# MethaneFlux.net
KiCad netlist of a schematic drawn in EAGLE
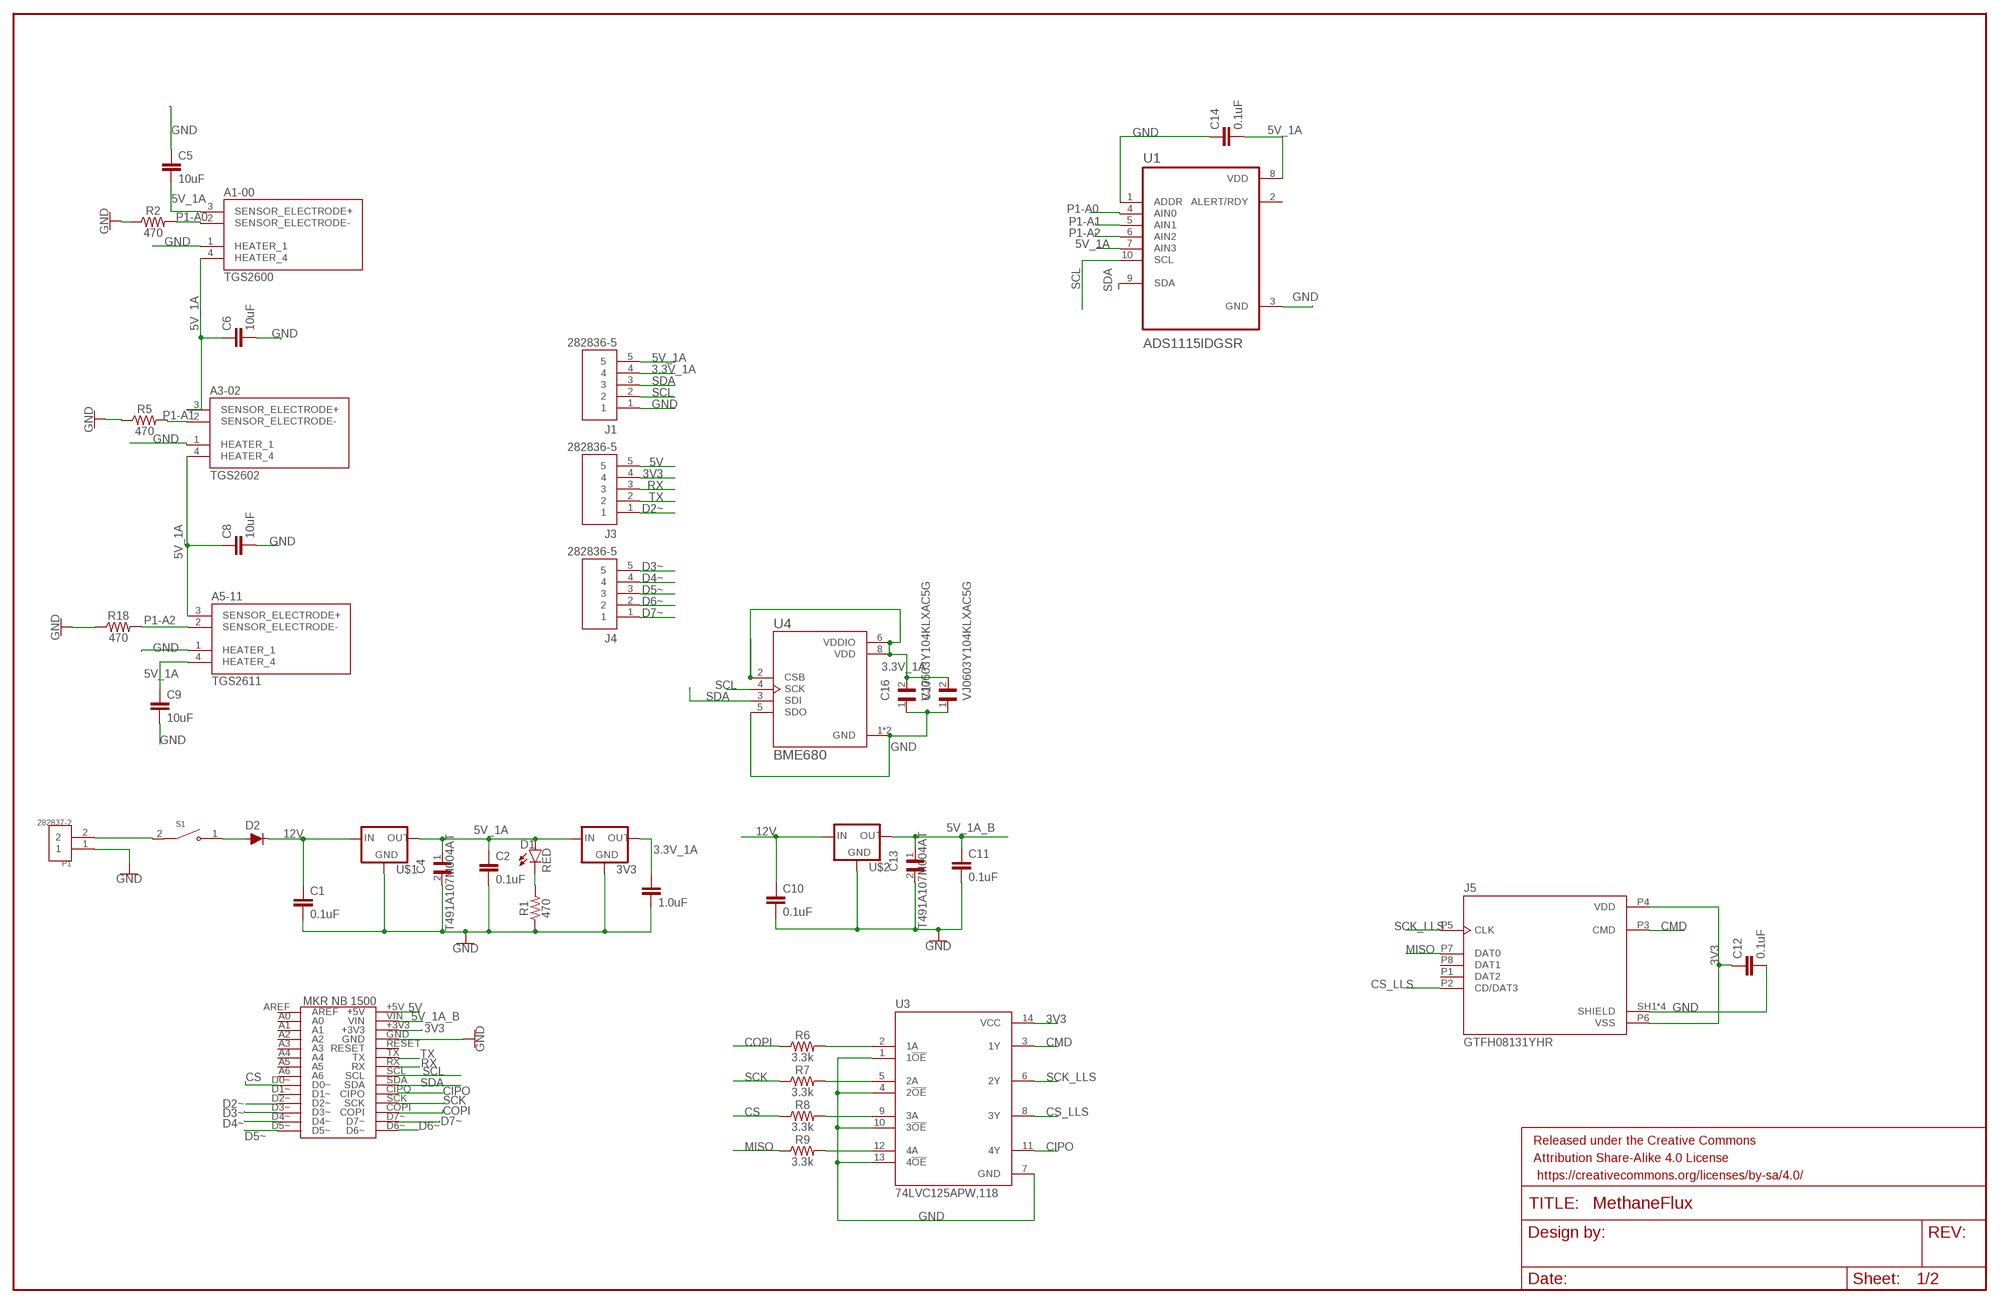
[diagram p0: schematic, sheet 1]
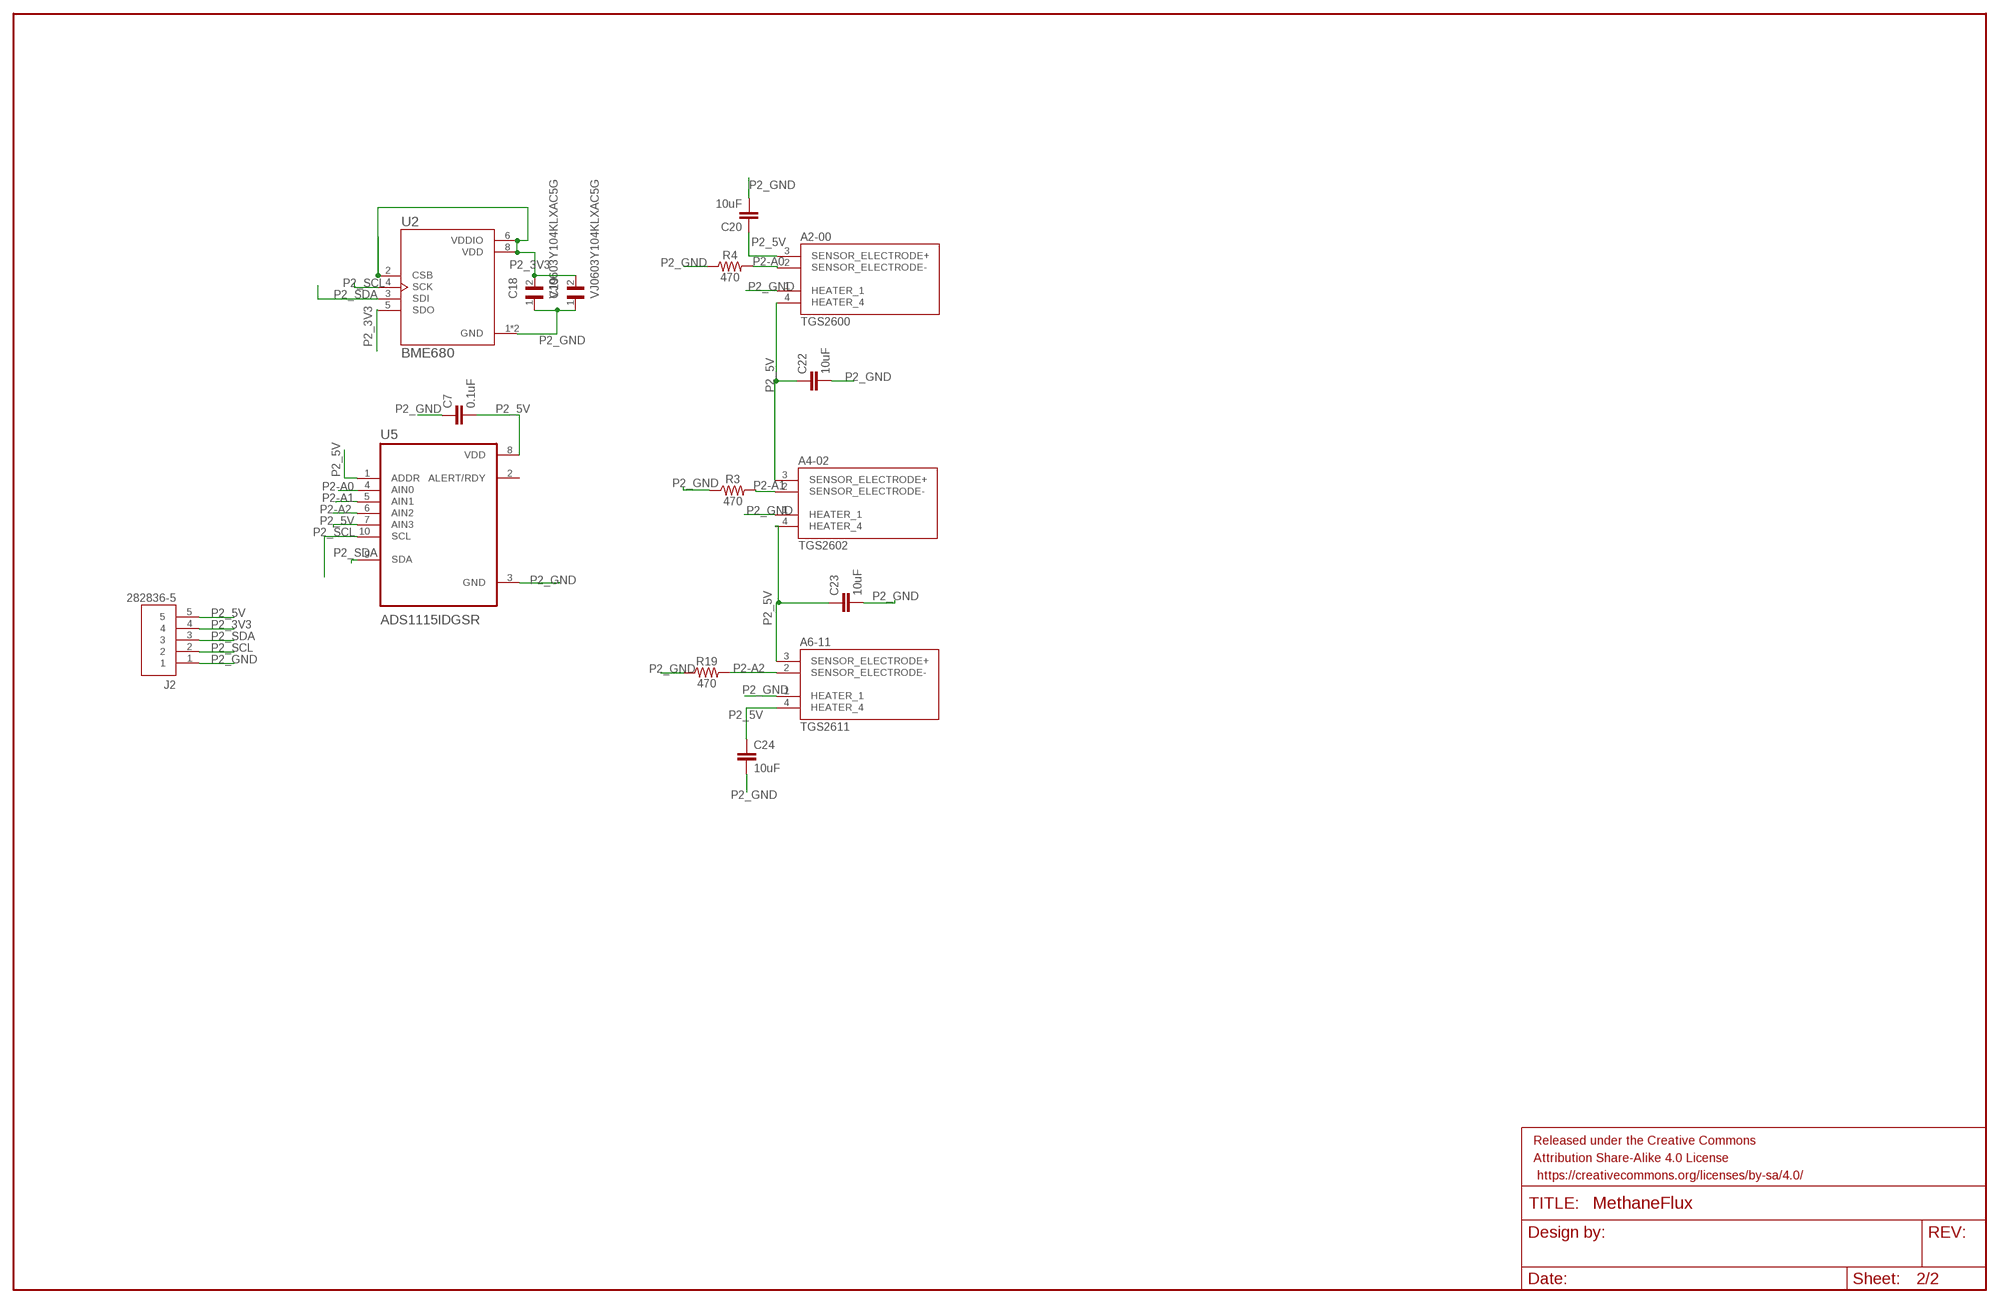
[diagram p1: schematic, sheet 2]

(export (version "E")
  (design (tool "Eeschema 10.0.6"))
  (components
    (comp (ref "A2-00")
      (value "TGS2600")
      (footprint "eagle-import:TO255P920H830-4")
      (fields (field (name "MF") "Figaro"))
      (libsource (lib "eagle-import") (part "TGS2600"))
    )
    (comp (ref "A4-02")
      (value "TGS2602")
      (footprint "eagle-import:TGS2602")
      (libsource (lib "eagle-import") (part "TGS2602"))
    )
    (comp (ref "A6-11")
      (value "TGS2611")
      (footprint "eagle-import:TGS2611")
      (libsource (lib "eagle-import") (part "TGS2611"))
    )
    (comp (ref "C7")
      (value "0.1uF")
      (footprint "eagle-import:0603")
      (libsource (lib "eagle-import") (part "0.1UF-0603-25V-5%"))
    )
    (comp (ref "C18")
      (value "VJ0603Y104KLXAC5G")
      (footprint "eagle-import:CAPC1608X92N")
      (fields (field (name "MF") "Vishay"))
      (libsource (lib "eagle-import") (part "VJ0603Y104KLXAC5G"))
    )
    (comp (ref "C19")
      (value "VJ0603Y104KLXAC5G")
      (footprint "eagle-import:CAPC1608X92N")
      (fields (field (name "MF") "Vishay"))
      (libsource (lib "eagle-import") (part "VJ0603Y104KLXAC5G"))
    )
    (comp (ref "C20")
      (value "10uF")
      (footprint "eagle-import:0603")
      (libsource (lib "eagle-import") (part "10UF-0603-6.3V-20%"))
    )
    (comp (ref "C22")
      (value "10uF")
      (footprint "eagle-import:0603")
      (libsource (lib "eagle-import") (part "10UF-0603-6.3V-20%"))
    )
    (comp (ref "C23")
      (value "10uF")
      (footprint "eagle-import:0603")
      (libsource (lib "eagle-import") (part "10UF-0603-6.3V-20%"))
    )
    (comp (ref "C24")
      (value "10uF")
      (footprint "eagle-import:0603")
      (libsource (lib "eagle-import") (part "10UF-0603-6.3V-20%"))
    )
    (comp (ref "FRAME2")
      (value "FRAME-LEDGER")
      (footprint "eagle-import:CREATIVE_COMMONS")
      (libsource (lib "eagle-import") (part "FRAME-LEDGER"))
    )
    (comp (ref "J2")
      (value "282836-5")
      (footprint "eagle-import:TE_282836-5")
      (fields (field (name "MF") "TE Connectivity"))
      (libsource (lib "eagle-import") (part "282836-5"))
    )
    (comp (ref "R3")
      (value "470")
      (footprint "eagle-import:0603")
      (libsource (lib "eagle-import") (part "470OHM-0603-1/10W-1%"))
    )
    (comp (ref "R4")
      (value "470")
      (footprint "eagle-import:0603")
      (libsource (lib "eagle-import") (part "470OHM-0603-1/10W-1%"))
    )
    (comp (ref "R19")
      (value "470")
      (footprint "eagle-import:0603")
      (libsource (lib "eagle-import") (part "470OHM-0603-1/10W-1%"))
    )
    (comp (ref "U2")
      (value "BME680")
      (footprint "eagle-import:PSON80P300X300X100-8N")
      (fields (field (name "MF") "Bosch Sensortec"))
      (libsource (lib "eagle-import") (part "BME680"))
    )
    (comp (ref "U5")
      (value "ADS1115IDGSR")
      (footprint "eagle-import:SOP50P490X110-10N")
      (fields (field (name "MF") "Texas Instruments"))
      (libsource (lib "eagle-import") (part "ADS1115IDGSR"))
    )
    (comp (ref "3V3")
      (value "V_REG_LD1117VXXLD1117-SMD")
      (footprint "eagle-import:SOT223")
      (libsource (lib "eagle-import") (part "V_REG_LD1117VXXLD1117-SMD"))
    )
    (comp (ref "A1-00")
      (value "TGS2600")
      (footprint "eagle-import:TO255P920H830-4")
      (fields (field (name "MF") "Figaro"))
      (libsource (lib "eagle-import") (part "TGS2600"))
    )
    (comp (ref "A3-02")
      (value "TGS2602")
      (footprint "eagle-import:TGS2602")
      (libsource (lib "eagle-import") (part "TGS2602"))
    )
    (comp (ref "A5-11")
      (value "TGS2611")
      (footprint "eagle-import:TGS2611")
      (libsource (lib "eagle-import") (part "TGS2611"))
    )
    (comp (ref "C1")
      (value "0.1uF")
      (footprint "eagle-import:0603")
      (libsource (lib "eagle-import") (part "0.1UF-0603-25V-5%"))
    )
    (comp (ref "C2")
      (value "0.1uF")
      (footprint "eagle-import:0603")
      (libsource (lib "eagle-import") (part "0.1UF-0603-25V-5%"))
    )
    (comp (ref "C3")
      (value "1.0uF")
      (footprint "eagle-import:0603")
      (libsource (lib "eagle-import") (part "1.0UF-0603-16V-10%"))
    )
    (comp (ref "C4")
      (value "T491A107M004AT")
      (footprint "eagle-import:CAPC3216X110N")
      (fields (field (name "MF") "KEMET"))
      (libsource (lib "eagle-import") (part "T491A107M004AT"))
    )
    (comp (ref "C5")
      (value "10uF")
      (footprint "eagle-import:0603")
      (libsource (lib "eagle-import") (part "10UF-0603-6.3V-20%"))
    )
    (comp (ref "C6")
      (value "10uF")
      (footprint "eagle-import:0603")
      (libsource (lib "eagle-import") (part "10UF-0603-6.3V-20%"))
    )
    (comp (ref "C8")
      (value "10uF")
      (footprint "eagle-import:0603")
      (libsource (lib "eagle-import") (part "10UF-0603-6.3V-20%"))
    )
    (comp (ref "C9")
      (value "10uF")
      (footprint "eagle-import:0603")
      (libsource (lib "eagle-import") (part "10UF-0603-6.3V-20%"))
    )
    (comp (ref "C10")
      (value "0.1uF")
      (footprint "eagle-import:0603")
      (libsource (lib "eagle-import") (part "0.1UF-0603-25V-5%"))
    )
    (comp (ref "C11")
      (value "0.1uF")
      (footprint "eagle-import:0603")
      (libsource (lib "eagle-import") (part "0.1UF-0603-25V-5%"))
    )
    (comp (ref "C12")
      (value "0.1uF")
      (footprint "eagle-import:0603")
      (libsource (lib "eagle-import") (part "0.1UF-0603-25V-5%"))
    )
    (comp (ref "C13")
      (value "T491A107M004AT")
      (footprint "eagle-import:CAPC3216X110N")
      (fields (field (name "MF") "KEMET"))
      (libsource (lib "eagle-import") (part "T491A107M004AT"))
    )
    (comp (ref "C14")
      (value "0.1uF")
      (footprint "eagle-import:0603")
      (libsource (lib "eagle-import") (part "0.1UF-0603-25V-5%"))
    )
    (comp (ref "C16")
      (value "VJ0603Y104KLXAC5G")
      (footprint "eagle-import:CAPC1608X92N")
      (fields (field (name "MF") "Vishay"))
      (libsource (lib "eagle-import") (part "VJ0603Y104KLXAC5G"))
    )
    (comp (ref "C17")
      (value "VJ0603Y104KLXAC5G")
      (footprint "eagle-import:CAPC1608X92N")
      (fields (field (name "MF") "Vishay"))
      (libsource (lib "eagle-import") (part "VJ0603Y104KLXAC5G"))
    )
    (comp (ref "D1")
      (value "RED")
      (footprint "eagle-import:LED-0603")
      (libsource (lib "eagle-import") (part "LED-RED0603"))
    )
    (comp (ref "D2")
      (value "200mA/100V/1V")
      (footprint "eagle-import:DIODE-1N4148")
      (libsource (lib "eagle-import") (part "DIODE-1N4148"))
    )
    (comp (ref "FRAME1")
      (value "FRAME-LEDGER")
      (footprint "eagle-import:CREATIVE_COMMONS")
      (libsource (lib "eagle-import") (part "FRAME-LEDGER"))
    )
    (comp (ref "J1")
      (value "282836-5")
      (footprint "eagle-import:TE_282836-5")
      (fields (field (name "MF") "TE Connectivity"))
      (libsource (lib "eagle-import") (part "282836-5"))
    )
    (comp (ref "J3")
      (value "282836-5")
      (footprint "eagle-import:TE_282836-5")
      (fields (field (name "MF") "TE Connectivity"))
      (libsource (lib "eagle-import") (part "282836-5"))
    )
    (comp (ref "J4")
      (value "282836-5")
      (footprint "eagle-import:TE_282836-5")
      (fields (field (name "MF") "TE Connectivity"))
      (libsource (lib "eagle-import") (part "282836-5"))
    )
    (comp (ref "J5")
      (value "GTFH08131YHR")
      (footprint "eagle-import:AMPHENOL_GTFH08131YHR")
      (fields (field (name "MF") "Amphenol ICC"))
      (libsource (lib "eagle-import") (part "GTFH08131YHR"))
    )
    (comp (ref "P1")
      (value "282837-2")
      (footprint "eagle-import:TE_282837-2")
      (fields (field (name "MF") "TE Connectivity"))
      (libsource (lib "eagle-import") (part "282837-2"))
    )
    (comp (ref "R1")
      (value "470")
      (footprint "eagle-import:0603")
      (libsource (lib "eagle-import") (part "470OHM-0603-1/10W-1%"))
    )
    (comp (ref "R2")
      (value "470")
      (footprint "eagle-import:0603")
      (libsource (lib "eagle-import") (part "470OHM-0603-1/10W-1%"))
    )
    (comp (ref "R5")
      (value "470")
      (footprint "eagle-import:0603")
      (libsource (lib "eagle-import") (part "470OHM-0603-1/10W-1%"))
    )
    (comp (ref "R6")
      (value "3.3k")
      (footprint "eagle-import:0603")
      (libsource (lib "eagle-import") (part "3.3KOHM-0603-1/10W-1%"))
    )
    (comp (ref "R7")
      (value "3.3k")
      (footprint "eagle-import:0603")
      (libsource (lib "eagle-import") (part "3.3KOHM-0603-1/10W-1%"))
    )
    (comp (ref "R8")
      (value "3.3k")
      (footprint "eagle-import:0603")
      (libsource (lib "eagle-import") (part "3.3KOHM-0603-1/10W-1%"))
    )
    (comp (ref "R9")
      (value "3.3k")
      (footprint "eagle-import:0603")
      (libsource (lib "eagle-import") (part "3.3KOHM-0603-1/10W-1%"))
    )
    (comp (ref "R18")
      (value "470")
      (footprint "eagle-import:0603")
      (libsource (lib "eagle-import") (part "470OHM-0603-1/10W-1%"))
    )
    (comp (ref "S1")
      (value "RB141C1100")
      (footprint "eagle-import:SW_RB141C1100")
      (fields (field (name "MF") "E-Switch"))
      (libsource (lib "eagle-import") (part "RB141C1100"))
    )
    (comp (ref "U$1")
      (value "V_REG_LD1117VXXLD1117-SMD")
      (footprint "eagle-import:SOT223")
      (libsource (lib "eagle-import") (part "V_REG_LD1117VXXLD1117-SMD"))
    )
    (comp (ref "U$2")
      (value "V_REG_LD1117VXXLD1117-SMD")
      (footprint "eagle-import:SOT223")
      (libsource (lib "eagle-import") (part "V_REG_LD1117VXXLD1117-SMD"))
    )
    (comp (ref "U$5")
      (value "MKRNB1500")
      (footprint "eagle-import:MRKNB1500")
      (libsource (lib "eagle-import") (part "MKRNB1500"))
    )
    (comp (ref "U1")
      (value "ADS1115IDGSR")
      (footprint "eagle-import:SOP50P490X110-10N")
      (fields (field (name "MF") "Texas Instruments"))
      (libsource (lib "eagle-import") (part "ADS1115IDGSR"))
    )
    (comp (ref "U3")
      (value "74LVC125APW,118")
      (footprint "eagle-import:IC_74LVC125APW,118")
      (fields (field (name "MF") "Nexperia USA Inc."))
      (libsource (lib "eagle-import") (part "74LVC125APW,118"))
    )
    (comp (ref "U4")
      (value "BME680")
      (footprint "eagle-import:PSON80P300X300X100-8N")
      (fields (field (name "MF") "Bosch Sensortec"))
      (libsource (lib "eagle-import") (part "BME680"))
    )
  )
  (nets
    (net (code "1") (name "3.3V_1A") (class "Default")
      (node (ref "3V3") (pin "2") (pinfunction "OUT_2") (pintype "passive"))
      (node (ref "C16") (pin "2") (pinfunction "2_2") (pintype "passive"))
      (node (ref "C17") (pin "2") (pinfunction "2_2") (pintype "passive"))
      (node (ref "C3") (pin "1") (pinfunction "1_1") (pintype "passive"))
      (node (ref "J1") (pin "4") (pinfunction "4_4") (pintype "passive"))
      (node (ref "U4") (pin "2") (pinfunction "CSB_2") (pintype "input"))
      (node (ref "U4") (pin "6") (pinfunction "VDDIO_6") (pintype "power_in"))
      (node (ref "U4") (pin "8") (pinfunction "VDD_8") (pintype "power_in"))
    )
    (net (code "2") (name "3V3") (class "Default")
      (node (ref "C12") (pin "1") (pinfunction "1_1") (pintype "passive"))
      (node (ref "J3") (pin "4") (pinfunction "4_4") (pintype "passive"))
      (node (ref "J5") (pin "P4") (pinfunction "VDD_P4") (pintype "power_in"))
      (node (ref "J5") (pin "P6") (pinfunction "VSS_P6") (pintype "power_in"))
      (node (ref "U$5") (pin "+3V3") (pinfunction "+3V3_+3V3") (pintype "bidirectional"))
      (node (ref "U3") (pin "14") (pinfunction "VCC_14") (pintype "power_in"))
    )
    (net (code "3") (name "5V") (class "Default")
      (node (ref "J3") (pin "5") (pinfunction "5_5") (pintype "passive"))
      (node (ref "U$5") (pin "+5V") (pinfunction "+5V_+5V") (pintype "bidirectional"))
    )
    (net (code "4") (name "5V_1A") (class "Default")
      (node (ref "3V3") (pin "3") (pinfunction "IN_3") (pintype "input"))
      (node (ref "A1-00") (pin "3") (pinfunction "SENSOR_ELECTRODE+_3") (pintype "passive"))
      (node (ref "A1-00") (pin "4") (pinfunction "HEATER_4_4") (pintype "passive"))
      (node (ref "A3-02") (pin "3") (pinfunction "SENSOR_ELECTRODE+_3") (pintype "passive"))
      (node (ref "A3-02") (pin "4") (pinfunction "HEATER_4_4") (pintype "passive"))
      (node (ref "A5-11") (pin "3") (pinfunction "SENSOR_ELECTRODE+_3") (pintype "passive"))
      (node (ref "A5-11") (pin "4") (pinfunction "HEATER_4_4") (pintype "passive"))
      (node (ref "C14") (pin "2") (pinfunction "2_2") (pintype "passive"))
      (node (ref "C2") (pin "1") (pinfunction "1_1") (pintype "passive"))
      (node (ref "C4") (pin "1") (pinfunction "1_1") (pintype "passive"))
      (node (ref "C5") (pin "2") (pinfunction "2_2") (pintype "passive"))
      (node (ref "C6") (pin "1") (pinfunction "1_1") (pintype "passive"))
      (node (ref "C8") (pin "1") (pinfunction "1_1") (pintype "passive"))
      (node (ref "C9") (pin "1") (pinfunction "1_1") (pintype "passive"))
      (node (ref "D1") (pin "A") (pinfunction "A_A") (pintype "passive"))
      (node (ref "J1") (pin "5") (pinfunction "5_5") (pintype "passive"))
      (node (ref "U$1") (pin "2") (pinfunction "OUT_2") (pintype "passive"))
      (node (ref "U1") (pin "7") (pinfunction "AIN3_7") (pintype "input"))
      (node (ref "U1") (pin "8") (pinfunction "VDD_8") (pintype "power_in"))
    )
    (net (code "5") (name "5V_1A_B") (class "Default")
      (node (ref "C11") (pin "1") (pinfunction "1_1") (pintype "passive"))
      (node (ref "C13") (pin "1") (pinfunction "1_1") (pintype "passive"))
      (node (ref "U$2") (pin "2") (pinfunction "OUT_2") (pintype "passive"))
      (node (ref "U$5") (pin "VIN") (pinfunction "VIN_VIN") (pintype "bidirectional"))
    )
    (net (code "6") (name "12V") (class "Default")
      (node (ref "C1") (pin "1") (pinfunction "1_1") (pintype "passive"))
      (node (ref "C10") (pin "1") (pinfunction "1_1") (pintype "passive"))
      (node (ref "D2") (pin "C") (pinfunction "C_C") (pintype "passive"))
      (node (ref "U$1") (pin "3") (pinfunction "IN_3") (pintype "input"))
      (node (ref "U$2") (pin "3") (pinfunction "IN_3") (pintype "input"))
    )
    (net (code "7") (name "CIPO") (class "Default")
      (node (ref "U$5") (pin "CIPO") (pinfunction "CIPO_CIPO") (pintype "bidirectional"))
      (node (ref "U3") (pin "11") (pinfunction "4Y_11") (pintype "output"))
    )
    (net (code "8") (name "CMD") (class "Default")
      (node (ref "J5") (pin "P3") (pinfunction "CMD_P3") (pintype "bidirectional"))
      (node (ref "U3") (pin "3") (pinfunction "1Y_3") (pintype "output"))
    )
    (net (code "9") (name "COPI") (class "Default")
      (node (ref "R6") (pin "1") (pinfunction "1_1") (pintype "passive"))
      (node (ref "U$5") (pin "COPI") (pinfunction "COPI_COPI") (pintype "bidirectional"))
    )
    (net (code "10") (name "CS") (class "Default")
      (node (ref "R8") (pin "1") (pinfunction "1_1") (pintype "passive"))
      (node (ref "U$5") (pin "D0~") (pinfunction "D0~{}_D0~") (pintype "bidirectional"))
    )
    (net (code "11") (name "CS_LLS") (class "Default")
      (node (ref "J5") (pin "P2") (pinfunction "CD/DAT3_P2") (pintype "bidirectional"))
      (node (ref "U3") (pin "8") (pinfunction "3Y_8") (pintype "output"))
    )
    (net (code "12") (name "D2~{}") (class "Default")
      (node (ref "J3") (pin "1") (pinfunction "1_1") (pintype "passive"))
      (node (ref "U$5") (pin "D2~") (pinfunction "D2~{}_D2~") (pintype "bidirectional"))
    )
    (net (code "13") (name "D3~{}") (class "Default")
      (node (ref "J4") (pin "5") (pinfunction "5_5") (pintype "passive"))
      (node (ref "U$5") (pin "D3~") (pinfunction "D3~{}_D3~") (pintype "bidirectional"))
    )
    (net (code "14") (name "D4~{}") (class "Default")
      (node (ref "J4") (pin "4") (pinfunction "4_4") (pintype "passive"))
      (node (ref "U$5") (pin "D4~") (pinfunction "D4~{}_D4~") (pintype "bidirectional"))
    )
    (net (code "15") (name "D5~{}") (class "Default")
      (node (ref "J4") (pin "3") (pinfunction "3_3") (pintype "passive"))
      (node (ref "U$5") (pin "D5~") (pinfunction "D5~{}_D5~") (pintype "bidirectional"))
    )
    (net (code "16") (name "D6~{}") (class "Default")
      (node (ref "J4") (pin "2") (pinfunction "2_2") (pintype "passive"))
      (node (ref "U$5") (pin "D6~") (pinfunction "D6~{}_D6~") (pintype "bidirectional"))
    )
    (net (code "17") (name "D7~{}") (class "Default")
      (node (ref "J4") (pin "1") (pinfunction "1_1") (pintype "passive"))
      (node (ref "U$5") (pin "D7~") (pinfunction "D7~{}_D7~") (pintype "bidirectional"))
    )
    (net (code "18") (name "GND") (class "Default")
      (node (ref "3V3") (pin "1") (pinfunction "GND_1") (pintype "input"))
      (node (ref "A1-00") (pin "1") (pinfunction "HEATER_1_1") (pintype "passive"))
      (node (ref "A3-02") (pin "1") (pinfunction "HEATER_1_1") (pintype "passive"))
      (node (ref "A5-11") (pin "1") (pinfunction "HEATER_1_1") (pintype "passive"))
      (node (ref "C1") (pin "2") (pinfunction "2_2") (pintype "passive"))
      (node (ref "C10") (pin "2") (pinfunction "2_2") (pintype "passive"))
      (node (ref "C11") (pin "2") (pinfunction "2_2") (pintype "passive"))
      (node (ref "C12") (pin "2") (pinfunction "2_2") (pintype "passive"))
      (node (ref "C13") (pin "2") (pinfunction "2_2") (pintype "passive"))
      (node (ref "C14") (pin "1") (pinfunction "1_1") (pintype "passive"))
      (node (ref "C16") (pin "1") (pinfunction "1_1") (pintype "passive"))
      (node (ref "C17") (pin "1") (pinfunction "1_1") (pintype "passive"))
      (node (ref "C2") (pin "2") (pinfunction "2_2") (pintype "passive"))
      (node (ref "C3") (pin "2") (pinfunction "2_2") (pintype "passive"))
      (node (ref "C4") (pin "2") (pinfunction "2_2") (pintype "passive"))
      (node (ref "C5") (pin "1") (pinfunction "1_1") (pintype "passive"))
      (node (ref "C6") (pin "2") (pinfunction "2_2") (pintype "passive"))
      (node (ref "C8") (pin "2") (pinfunction "2_2") (pintype "passive"))
      (node (ref "C9") (pin "2") (pinfunction "2_2") (pintype "passive"))
      (node (ref "J1") (pin "1") (pinfunction "1_1") (pintype "passive"))
      (node (ref "J5") (pin "SH1") (pinfunction "SHIELD_SH1") (pintype "power_in"))
      (node (ref "J5") (pin "SH2") (pinfunction "SHIELD_SH2") (pintype "power_in"))
      (node (ref "J5") (pin "SH3") (pinfunction "SHIELD_SH3") (pintype "power_in"))
      (node (ref "J5") (pin "SH4") (pinfunction "SHIELD_SH4") (pintype "power_in"))
      (node (ref "P1") (pin "1") (pinfunction "1_1") (pintype "passive"))
      (node (ref "R1") (pin "1") (pinfunction "1_1") (pintype "passive"))
      (node (ref "R18") (pin "1") (pinfunction "1_1") (pintype "passive"))
      (node (ref "R2") (pin "1") (pinfunction "1_1") (pintype "passive"))
      (node (ref "R5") (pin "1") (pinfunction "1_1") (pintype "passive"))
      (node (ref "U$1") (pin "1") (pinfunction "GND_1") (pintype "input"))
      (node (ref "U$2") (pin "1") (pinfunction "GND_1") (pintype "input"))
      (node (ref "U$5") (pin "GND") (pinfunction "GND_GND") (pintype "bidirectional"))
      (node (ref "U1") (pin "1") (pinfunction "ADDR_1") (pintype "input"))
      (node (ref "U1") (pin "3") (pinfunction "GND_3") (pintype "power_in"))
      (node (ref "U3") (pin "1") (pinfunction "1~{OE}_1") (pintype "input"))
      (node (ref "U3") (pin "10") (pinfunction "3~{OE}_10") (pintype "input"))
      (node (ref "U3") (pin "13") (pinfunction "4~{OE}_13") (pintype "input"))
      (node (ref "U3") (pin "4") (pinfunction "2~{OE}_4") (pintype "input"))
      (node (ref "U3") (pin "7") (pinfunction "GND_7") (pintype "power_in"))
      (node (ref "U4") (pin "1") (pinfunction "GND_1") (pintype "power_in"))
      (node (ref "U4") (pin "5") (pinfunction "SDO_5") (pintype "bidirectional"))
      (node (ref "U4") (pin "7") (pinfunction "GND_7") (pintype "power_in"))
    )
    (net (code "19") (name "MISO") (class "Default")
      (node (ref "J5") (pin "P7") (pinfunction "DAT0_P7") (pintype "bidirectional"))
      (node (ref "R9") (pin "1") (pinfunction "1_1") (pintype "passive"))
    )
    (net (code "20") (name "Net-(D1-PadC)") (class "Default")
      (node (ref "D1") (pin "C") (pinfunction "C_C") (pintype "passive"))
      (node (ref "R1") (pin "2") (pinfunction "2_2") (pintype "passive"))
    )
    (net (code "21") (name "Net-(D2-PadA)") (class "Default")
      (node (ref "D2") (pin "A") (pinfunction "A_A") (pintype "passive"))
      (node (ref "S1") (pin "1") (pinfunction "1_1") (pintype "passive"))
    )
    (net (code "22") (name "Net-(P1-Pad2)") (class "Default")
      (node (ref "P1") (pin "2") (pinfunction "2_2") (pintype "passive"))
      (node (ref "S1") (pin "2") (pinfunction "2_2") (pintype "passive"))
    )
    (net (code "23") (name "Net-(U3-1A)") (class "Default")
      (node (ref "R6") (pin "2") (pinfunction "2_2") (pintype "passive"))
      (node (ref "U3") (pin "2") (pinfunction "1A_2") (pintype "input"))
    )
    (net (code "24") (name "Net-(U3-2A)") (class "Default")
      (node (ref "R7") (pin "2") (pinfunction "2_2") (pintype "passive"))
      (node (ref "U3") (pin "5") (pinfunction "2A_5") (pintype "input"))
    )
    (net (code "25") (name "Net-(U3-3A)") (class "Default")
      (node (ref "R8") (pin "2") (pinfunction "2_2") (pintype "passive"))
      (node (ref "U3") (pin "9") (pinfunction "3A_9") (pintype "input"))
    )
    (net (code "26") (name "Net-(U3-4A)") (class "Default")
      (node (ref "R9") (pin "2") (pinfunction "2_2") (pintype "passive"))
      (node (ref "U3") (pin "12") (pinfunction "4A_12") (pintype "input"))
    )
    (net (code "27") (name "P1-A0") (class "Default")
      (node (ref "A1-00") (pin "2") (pinfunction "SENSOR_ELECTRODE-_2") (pintype "passive"))
      (node (ref "R2") (pin "2") (pinfunction "2_2") (pintype "passive"))
      (node (ref "U1") (pin "4") (pinfunction "AIN0_4") (pintype "input"))
    )
    (net (code "28") (name "P1-A1") (class "Default")
      (node (ref "A3-02") (pin "2") (pinfunction "SENSOR_ELECTRODE-_2") (pintype "passive"))
      (node (ref "R5") (pin "2") (pinfunction "2_2") (pintype "passive"))
      (node (ref "U1") (pin "5") (pinfunction "AIN1_5") (pintype "input"))
    )
    (net (code "29") (name "P1-A2") (class "Default")
      (node (ref "A5-11") (pin "2") (pinfunction "SENSOR_ELECTRODE-_2") (pintype "passive"))
      (node (ref "R18") (pin "2") (pinfunction "2_2") (pintype "passive"))
      (node (ref "U1") (pin "6") (pinfunction "AIN2_6") (pintype "input"))
    )
    (net (code "30") (name "P2-A0") (class "Default")
      (node (ref "A2-00") (pin "2") (pinfunction "SENSOR_ELECTRODE-_2") (pintype "passive"))
      (node (ref "R4") (pin "2") (pinfunction "2_2") (pintype "passive"))
      (node (ref "U5") (pin "4") (pinfunction "AIN0_4") (pintype "input"))
    )
    (net (code "31") (name "P2-A1") (class "Default")
      (node (ref "A4-02") (pin "2") (pinfunction "SENSOR_ELECTRODE-_2") (pintype "passive"))
      (node (ref "R3") (pin "2") (pinfunction "2_2") (pintype "passive"))
      (node (ref "U5") (pin "5") (pinfunction "AIN1_5") (pintype "input"))
    )
    (net (code "32") (name "P2-A2") (class "Default")
      (node (ref "A6-11") (pin "2") (pinfunction "SENSOR_ELECTRODE-_2") (pintype "passive"))
      (node (ref "R19") (pin "2") (pinfunction "2_2") (pintype "passive"))
      (node (ref "U5") (pin "6") (pinfunction "AIN2_6") (pintype "input"))
    )
    (net (code "33") (name "P2_3V3") (class "Default")
      (node (ref "C18") (pin "2") (pinfunction "2_2") (pintype "passive"))
      (node (ref "C19") (pin "2") (pinfunction "2_2") (pintype "passive"))
      (node (ref "J2") (pin "4") (pinfunction "4_4") (pintype "passive"))
      (node (ref "U2") (pin "2") (pinfunction "CSB_2") (pintype "input"))
      (node (ref "U2") (pin "5") (pinfunction "SDO_5") (pintype "bidirectional"))
      (node (ref "U2") (pin "6") (pinfunction "VDDIO_6") (pintype "power_in"))
      (node (ref "U2") (pin "8") (pinfunction "VDD_8") (pintype "power_in"))
    )
    (net (code "34") (name "P2_5V") (class "Default")
      (node (ref "A2-00") (pin "3") (pinfunction "SENSOR_ELECTRODE+_3") (pintype "passive"))
      (node (ref "A2-00") (pin "4") (pinfunction "HEATER_4_4") (pintype "passive"))
      (node (ref "A4-02") (pin "3") (pinfunction "SENSOR_ELECTRODE+_3") (pintype "passive"))
      (node (ref "A4-02") (pin "4") (pinfunction "HEATER_4_4") (pintype "passive"))
      (node (ref "A6-11") (pin "3") (pinfunction "SENSOR_ELECTRODE+_3") (pintype "passive"))
      (node (ref "A6-11") (pin "4") (pinfunction "HEATER_4_4") (pintype "passive"))
      (node (ref "C20") (pin "1") (pinfunction "1_1") (pintype "passive"))
      (node (ref "C22") (pin "1") (pinfunction "1_1") (pintype "passive"))
      (node (ref "C23") (pin "1") (pinfunction "1_1") (pintype "passive"))
      (node (ref "C24") (pin "1") (pinfunction "1_1") (pintype "passive"))
      (node (ref "C7") (pin "2") (pinfunction "2_2") (pintype "passive"))
      (node (ref "J2") (pin "5") (pinfunction "5_5") (pintype "passive"))
      (node (ref "U5") (pin "1") (pinfunction "ADDR_1") (pintype "input"))
      (node (ref "U5") (pin "7") (pinfunction "AIN3_7") (pintype "input"))
      (node (ref "U5") (pin "8") (pinfunction "VDD_8") (pintype "power_in"))
    )
    (net (code "35") (name "P2_GND") (class "Default")
      (node (ref "A2-00") (pin "1") (pinfunction "HEATER_1_1") (pintype "passive"))
      (node (ref "A4-02") (pin "1") (pinfunction "HEATER_1_1") (pintype "passive"))
      (node (ref "A6-11") (pin "1") (pinfunction "HEATER_1_1") (pintype "passive"))
      (node (ref "C18") (pin "1") (pinfunction "1_1") (pintype "passive"))
      (node (ref "C19") (pin "1") (pinfunction "1_1") (pintype "passive"))
      (node (ref "C20") (pin "2") (pinfunction "2_2") (pintype "passive"))
      (node (ref "C22") (pin "2") (pinfunction "2_2") (pintype "passive"))
      (node (ref "C23") (pin "2") (pinfunction "2_2") (pintype "passive"))
      (node (ref "C24") (pin "2") (pinfunction "2_2") (pintype "passive"))
      (node (ref "C7") (pin "1") (pinfunction "1_1") (pintype "passive"))
      (node (ref "J2") (pin "1") (pinfunction "1_1") (pintype "passive"))
      (node (ref "R19") (pin "1") (pinfunction "1_1") (pintype "passive"))
      (node (ref "R3") (pin "1") (pinfunction "1_1") (pintype "passive"))
      (node (ref "R4") (pin "1") (pinfunction "1_1") (pintype "passive"))
      (node (ref "U2") (pin "1") (pinfunction "GND_1") (pintype "power_in"))
      (node (ref "U2") (pin "7") (pinfunction "GND_7") (pintype "power_in"))
      (node (ref "U5") (pin "3") (pinfunction "GND_3") (pintype "power_in"))
    )
    (net (code "36") (name "P2_SCL") (class "Default")
      (node (ref "J2") (pin "2") (pinfunction "2_2") (pintype "passive"))
      (node (ref "U2") (pin "4") (pinfunction "SCK_4") (pintype "input"))
      (node (ref "U5") (pin "10") (pinfunction "SCL_10") (pintype "input"))
    )
    (net (code "37") (name "P2_SDA") (class "Default")
      (node (ref "J2") (pin "3") (pinfunction "3_3") (pintype "passive"))
      (node (ref "U2") (pin "3") (pinfunction "SDI_3") (pintype "bidirectional"))
      (node (ref "U5") (pin "9") (pinfunction "SDA_9") (pintype "bidirectional"))
    )
    (net (code "38") (name "RX") (class "Default")
      (node (ref "J3") (pin "3") (pinfunction "3_3") (pintype "passive"))
      (node (ref "U$5") (pin "RX") (pinfunction "RX_RX") (pintype "bidirectional"))
    )
    (net (code "39") (name "SCK") (class "Default")
      (node (ref "R7") (pin "1") (pinfunction "1_1") (pintype "passive"))
      (node (ref "U$5") (pin "SCK") (pinfunction "SCK_SCK") (pintype "bidirectional"))
    )
    (net (code "40") (name "SCK_LLS") (class "Default")
      (node (ref "J5") (pin "P5") (pinfunction "CLK_P5") (pintype "bidirectional"))
      (node (ref "U3") (pin "6") (pinfunction "2Y_6") (pintype "output"))
    )
    (net (code "41") (name "SCL") (class "Default")
      (node (ref "J1") (pin "2") (pinfunction "2_2") (pintype "passive"))
      (node (ref "U$5") (pin "SCL") (pinfunction "SCL_SCL") (pintype "bidirectional"))
      (node (ref "U1") (pin "10") (pinfunction "SCL_10") (pintype "input"))
      (node (ref "U4") (pin "4") (pinfunction "SCK_4") (pintype "input"))
    )
    (net (code "42") (name "SDA") (class "Default")
      (node (ref "J1") (pin "3") (pinfunction "3_3") (pintype "passive"))
      (node (ref "U$5") (pin "SDA") (pinfunction "SDA_SDA") (pintype "bidirectional"))
      (node (ref "U1") (pin "9") (pinfunction "SDA_9") (pintype "bidirectional"))
      (node (ref "U4") (pin "3") (pinfunction "SDI_3") (pintype "bidirectional"))
    )
    (net (code "43") (name "TX") (class "Default")
      (node (ref "J3") (pin "2") (pinfunction "2_2") (pintype "passive"))
      (node (ref "U$5") (pin "TX") (pinfunction "TX_TX") (pintype "bidirectional"))
    )
    (net (code "44") (name "unconnected-(J5-DAT1-PadP8)") (class "Default")
      (node (ref "J5") (pin "P8") (pinfunction "DAT1_P8") (pintype "bidirectional"))
    )
    (net (code "45") (name "unconnected-(J5-DAT2-PadP1)") (class "Default")
      (node (ref "J5") (pin "P1") (pinfunction "DAT2_P1") (pintype "bidirectional"))
    )
    (net (code "46") (name "unconnected-(U$5-D1~{}-PadD1~)") (class "Default")
      (node (ref "U$5") (pin "D1~") (pinfunction "D1~{}_D1~") (pintype "bidirectional"))
    )
    (net (code "47") (name "unconnected-(U$5-PadA0)") (class "Default")
      (node (ref "U$5") (pin "A0") (pinfunction "A0_A0") (pintype "bidirectional"))
    )
    (net (code "48") (name "unconnected-(U$5-PadA1)") (class "Default")
      (node (ref "U$5") (pin "A1") (pinfunction "A1_A1") (pintype "bidirectional"))
    )
    (net (code "49") (name "unconnected-(U$5-PadA2)") (class "Default")
      (node (ref "U$5") (pin "A2") (pinfunction "A2_A2") (pintype "bidirectional"))
    )
    (net (code "50") (name "unconnected-(U$5-PadA3)") (class "Default")
      (node (ref "U$5") (pin "A3") (pinfunction "A3_A3") (pintype "bidirectional"))
    )
    (net (code "51") (name "unconnected-(U$5-PadA4)") (class "Default")
      (node (ref "U$5") (pin "A4") (pinfunction "A4_A4") (pintype "bidirectional"))
    )
    (net (code "52") (name "unconnected-(U$5-PadA5)") (class "Default")
      (node (ref "U$5") (pin "A5") (pinfunction "A5_A5") (pintype "bidirectional"))
    )
    (net (code "53") (name "unconnected-(U$5-PadA6)") (class "Default")
      (node (ref "U$5") (pin "A6") (pinfunction "A6_A6") (pintype "bidirectional"))
    )
    (net (code "54") (name "unconnected-(U$5-PadAREF)") (class "Default")
      (node (ref "U$5") (pin "AREF") (pinfunction "AREF_AREF") (pintype "bidirectional"))
    )
    (net (code "55") (name "unconnected-(U$5-PadRESET)") (class "Default")
      (node (ref "U$5") (pin "RESET") (pinfunction "RESET_RESET") (pintype "bidirectional"))
    )
    (net (code "56") (name "unconnected-(U1-ALERT{slash}RDY-Pad2)") (class "Default")
      (node (ref "U1") (pin "2") (pinfunction "ALERT/RDY_2") (pintype "output"))
    )
    (net (code "57") (name "unconnected-(U5-ALERT{slash}RDY-Pad2)") (class "Default")
      (node (ref "U5") (pin "2") (pinfunction "ALERT/RDY_2") (pintype "output"))
    )
  )
)
